# STM32WB55CGU6.net
KiCad netlist of a schematic drawn in Altium Designer
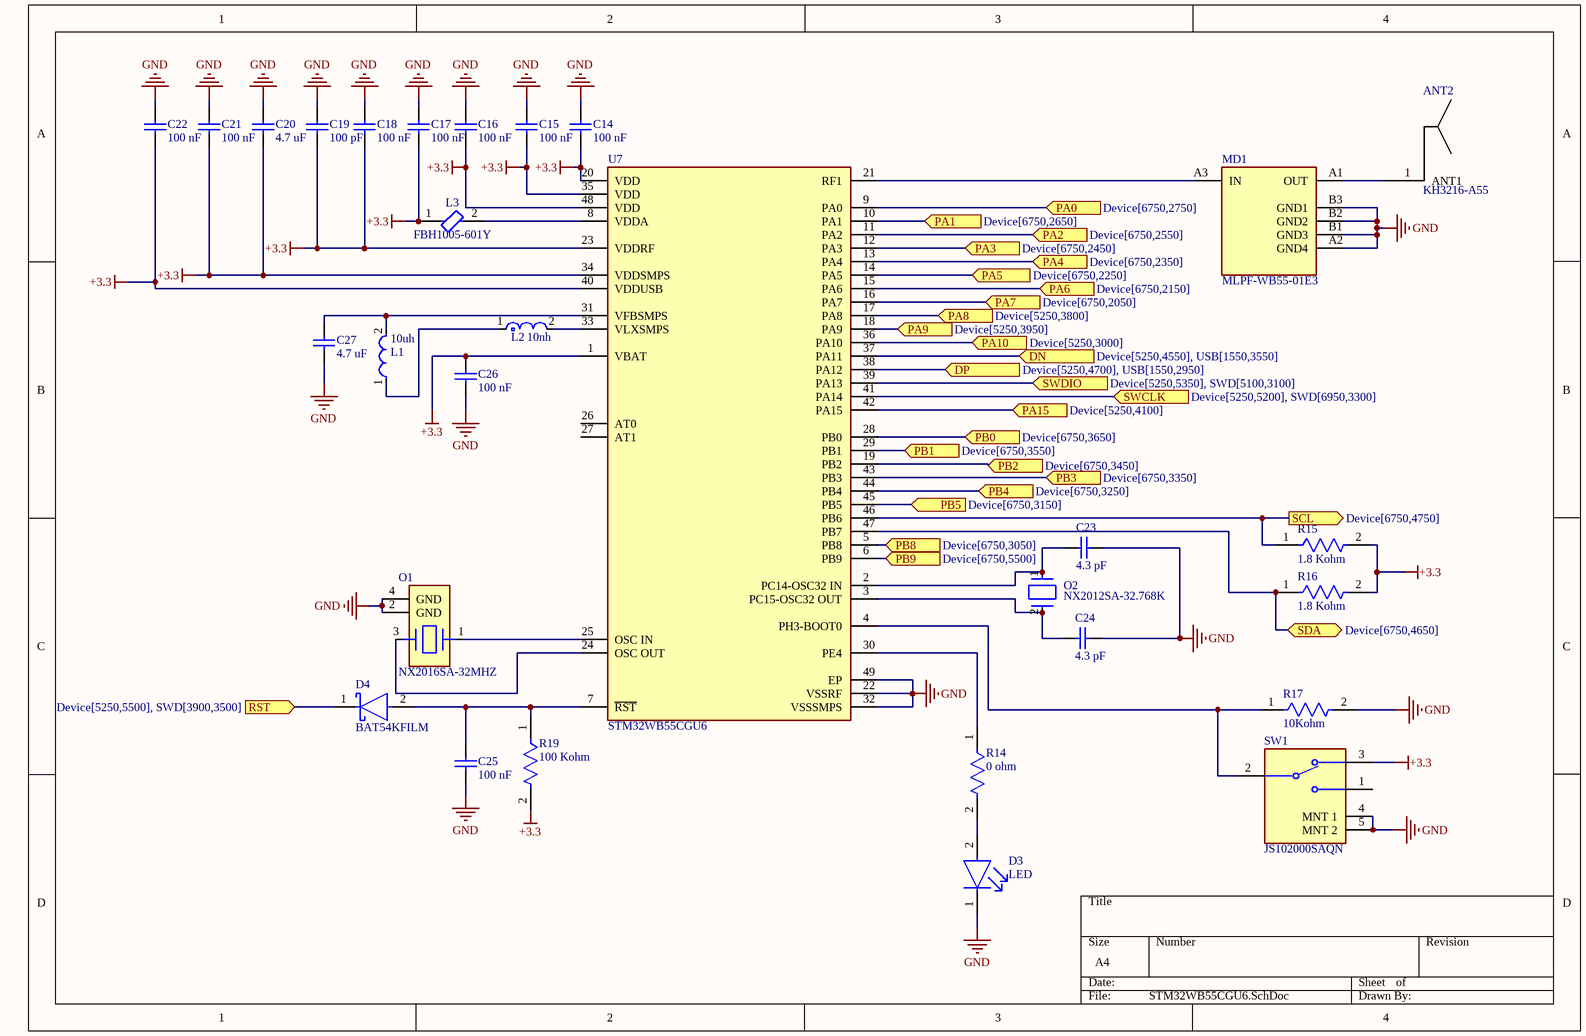
[diagram p0: STM32WB55CGU6.SchDoc]

(export (version "E")
  (design (tool "Eeschema 10.0.6"))
  (components
    (comp (ref "10uh")
      (value "L1")
      (footprint "FP-LQW15DN_00-MFG")
      (description "FIXED IND 10UH 120MA 5.405OHM")
      (libsource (lib "Altium Content Vault") (part "725321dda6339637d4d059423bc1c3c"))
    )
    (comp (ref "ANT2")
      (value "KH3216-A55")
      (footprint "KH3216-A55")
      (libsource (lib "Custom.") (part "KH3216-A55"))
    )
    (comp (ref "C14")
      (value "100 nF")
      (footprint "CAPC1005X55X25NL05T10")
      (fields (field (name "MANUFACTURER") "Murata") (field (name "PART NUMBER") "GRM155F50J684ZE01D"))
      (libsource (lib "Altium Content Vault") (part "CAP"))
    )
    (comp (ref "C15")
      (value "100 nF")
      (footprint "CAPC1005X55X25NL05T10")
      (fields (field (name "MANUFACTURER") "Murata") (field (name "PART NUMBER") "GRM155F50J684ZE01D"))
      (libsource (lib "Altium Content Vault") (part "CAP"))
    )
    (comp (ref "C16")
      (value "100 nF")
      (footprint "CAPC1005X55X25NL05T10")
      (fields (field (name "MANUFACTURER") "Murata") (field (name "PART NUMBER") "GRM155F50J684ZE01D"))
      (libsource (lib "Altium Content Vault") (part "CAP"))
    )
    (comp (ref "C17")
      (value "100 nF")
      (footprint "CAPC1005X55X25NL05T10")
      (fields (field (name "MANUFACTURER") "Murata") (field (name "PART NUMBER") "GRM155F50J684ZE01D"))
      (libsource (lib "Altium Content Vault") (part "CAP"))
    )
    (comp (ref "C18")
      (value "100 nF")
      (footprint "CAPC1005X55X25NL05T10")
      (fields (field (name "MANUFACTURER") "Murata") (field (name "PART NUMBER") "GRM155F50J684ZE01D"))
      (libsource (lib "Altium Content Vault") (part "CAP"))
    )
    (comp (ref "C19")
      (value "100 pF")
      (footprint "CAPC1005X55X25NL05T10")
      (fields (field (name "MANUFACTURER") "Murata") (field (name "PART NUMBER") "GRM155F50J684ZE01D"))
      (libsource (lib "Altium Content Vault") (part "CAP"))
    )
    (comp (ref "C20")
      (value "4.7 uF")
      (footprint "CAPC1005X55X25NL05T10")
      (fields (field (name "MANUFACTURER") "Murata") (field (name "PART NUMBER") "GRM155F50J684ZE01D"))
      (libsource (lib "Altium Content Vault") (part "CAP"))
    )
    (comp (ref "C21")
      (value "100 nF")
      (footprint "CAPC1005X55X25NL05T10")
      (fields (field (name "MANUFACTURER") "Murata") (field (name "PART NUMBER") "GRM155F50J684ZE01D"))
      (libsource (lib "Altium Content Vault") (part "CAP"))
    )
    (comp (ref "C22")
      (value "100 nF")
      (footprint "CAPC1005X55X25NL05T10")
      (fields (field (name "MANUFACTURER") "Murata") (field (name "PART NUMBER") "GRM155F50J684ZE01D"))
      (libsource (lib "Altium Content Vault") (part "CAP"))
    )
    (comp (ref "C23")
      (value "4.3 pF")
      (footprint "CAPC1005X55X25NL05T10")
      (fields (field (name "MANUFACTURER") "Murata") (field (name "PART NUMBER") "GRM155F50J684ZE01D"))
      (libsource (lib "Altium Content Vault") (part "CAP"))
    )
    (comp (ref "C24")
      (value "4.3 pF")
      (footprint "CAPC1005X55X25NL05T10")
      (fields (field (name "MANUFACTURER") "Murata") (field (name "PART NUMBER") "GRM155F50J684ZE01D"))
      (libsource (lib "Altium Content Vault") (part "CAP"))
    )
    (comp (ref "C25")
      (value "100 nF")
      (footprint "CAPC1005X55X25NL05T10")
      (fields (field (name "MANUFACTURER") "Murata") (field (name "PART NUMBER") "GRM155F50J684ZE01D"))
      (libsource (lib "Altium Content Vault") (part "CAP"))
    )
    (comp (ref "C26")
      (value "100 nF")
      (footprint "CAPC1005X55X25NL05T10")
      (fields (field (name "MANUFACTURER") "Murata") (field (name "PART NUMBER") "GRM155F50J684ZE01D"))
      (libsource (lib "Altium Content Vault") (part "CAP"))
    )
    (comp (ref "C27")
      (value "4.7 uF")
      (footprint "CAPC1005X55X25NL05T10")
      (fields (field (name "MANUFACTURER") "Murata") (field (name "PART NUMBER") "GRM155F50J684ZE01D"))
      (libsource (lib "Altium Content Vault") (part "CAP"))
    )
    (comp (ref "D3")
      (value "LED")
      (footprint "FP-SML-P11MTT86-MFG")
      (description "LED YELLOW/GREEN CLEAR 1006 SMD")
      (libsource (lib "Altium Content Vault") (part "8706943c75ba83719d021d2fdc84c58"))
    )
    (comp (ref "D4")
      (value "BAT54KFILM")
      (footprint "FP-SOD-523-MFG")
      (description "DIODE SCHOTTKY 40V 300MA SOD523")
      (fields
        (field (name "OCTOPART") "https://octopart.com/bat54kfilm-stmicroelectronics-39618022")
        (field (name "MANUFACTURER") "STMicroelectronics")
      )
      (libsource (lib "Altium Content Vault") (part "1d6ec82d83fb6aee721767c19dac4b9"))
    )
    (comp (ref "L2")
      (value "10nh")
      (footprint "FP-LQG15WH_02-MFG")
      (description "Multilayer type Inductor for Automotive 10nH ±5% 0.19Ω 500mA 0402")
      (fields (field (name "TOLERANCE") "5%"))
      (libsource (lib "Altium Content Vault") (part "4cc4b267dca4c8e51f7102f422741d8"))
    )
    (comp (ref "L3")
      (value "FBH1005-601Y")
      (footprint "FP-BLM15-0_05-MFG")
      (description "Chip Ferrite Bead, 0402, 600Ω @ 100MHz, 0.52Ω, 25%, 300mA")
      (fields (field (name "TOLERANCE") "25%"))
      (libsource (lib "Altium Content Vault") (part "5f30dd21d616792df468990f7003faa"))
    )
    (comp (ref "MD1")
      (value "MLPF-WB55-01E3")
      (footprint "FP-MLPF-WB55-01E3-MFG")
      (description "RF FILTER LOW PASS 2.45GHZ 6SMD")
      (libsource (lib "Altium Content Vault") (part "51e28da9fe7b2e4e5e03ac85244eada"))
    )
    (comp (ref "O1")
      (value "NX2016SA-32MHZ")
      (footprint "FP-NX2016SA-MFG")
      (description "CRYSTAL 32.0000MHZ 8PF SMD")
      (libsource (lib "Altium Content Vault") (part "0d11ad3ca7be055efd3b4f344707230"))
    )
    (comp (ref "O2")
      (value "NX2012SA-32.768K")
      (footprint "FP-NX2012SA-MFG")
      (description "CRYSTAL 32.7680KHZ 12.5PF SMD")
      (libsource (lib "Altium Content Vault") (part "c23a69dc6c9e2f18f2079038eb95dd1"))
    )
    (comp (ref "R14")
      (value "0 ohm")
      (footprint "FP-RC1005-IPC_C")
      (description "Res Thick Film 0402 1.87kΩ 1% 0.063W ±100ppm/°C Molded SMD T/R")
      (fields (field (name "TOLERANCE") "1%"))
      (libsource (lib "Altium Content Vault") (part "1029c3af85768c4190bb7ad29bc67b5"))
    )
    (comp (ref "R15")
      (value "1.8 Kohm")
      (footprint "FP-RC1005-IPC_C")
      (description "Res Thick Film 0402 1.87kΩ 1% 0.063W ±100ppm/°C Molded SMD T/R")
      (fields (field (name "TOLERANCE") "1%"))
      (libsource (lib "Altium Content Vault") (part "1029c3af85768c4190bb7ad29bc67b5"))
    )
    (comp (ref "R16")
      (value "1.8 Kohm")
      (footprint "FP-RC1005-IPC_C")
      (description "Res Thick Film 0402 1.87kΩ 1% 0.063W ±100ppm/°C Molded SMD T/R")
      (fields (field (name "TOLERANCE") "1%"))
      (libsource (lib "Altium Content Vault") (part "1029c3af85768c4190bb7ad29bc67b5"))
    )
    (comp (ref "R17")
      (value "10Kohm")
      (footprint "FP-RC1005-IPC_C")
      (description "Res Thick Film 0402 1.87kΩ 1% 0.063W ±100ppm/°C Molded SMD T/R")
      (fields (field (name "TOLERANCE") "1%"))
      (libsource (lib "Altium Content Vault") (part "1029c3af85768c4190bb7ad29bc67b5"))
    )
    (comp (ref "R19")
      (value "100 Kohm")
      (footprint "FP-RC1005-IPC_C")
      (description "Res Thick Film 0402 1.87kΩ 1% 0.063W ±100ppm/°C Molded SMD T/R")
      (fields (field (name "TOLERANCE") "1%"))
      (libsource (lib "Altium Content Vault") (part "1029c3af85768c4190bb7ad29bc67b5"))
    )
    (comp (ref "SW1")
      (value "JS102000SAQN")
      (footprint "FP-JS102000SAQN-MFG")
      (description "SWITCH SLIDE SPDT 1MA 5V")
      (libsource (lib "Altium Content Vault") (part "6887e5fe807d9c5c2853bed39bc55bf"))
    )
    (comp (ref "U7")
      (value "STM32WB55CGU6")
      (footprint "FP-STM32WB55CGU6-MFG")
      (description "ULTRA-LOW-POWER DUAL CORE ARM CO")
      (fields
        (field (name "OCTOPART") "https://octopart.com/stm32wb55cgu6-stmicroelectronics-98750847")
        (field (name "MANUFACTURER") "STMicroelectronics")
      )
      (libsource (lib "Altium Content Vault") (part "9d9ca7f3567da95c474f3f549f05e68"))
    )
  )
  (nets
    (net (code "1") (name "+3.3") (class "Default")
      (node (ref "C14") (pin "1") (pinfunction "1_1") (pintype "passive"))
      (node (ref "C15") (pin "2") (pinfunction "2_2") (pintype "passive"))
      (node (ref "C16") (pin "1") (pinfunction "1_1") (pintype "passive"))
      (node (ref "C17") (pin "2") (pinfunction "2_2") (pintype "passive"))
      (node (ref "C18") (pin "1") (pinfunction "1_1") (pintype "passive"))
      (node (ref "C19") (pin "2") (pinfunction "2_2") (pintype "passive"))
      (node (ref "C20") (pin "2") (pinfunction "2_2") (pintype "passive"))
      (node (ref "C21") (pin "1") (pinfunction "1_1") (pintype "passive"))
      (node (ref "C22") (pin "2") (pinfunction "2_2") (pintype "passive"))
      (node (ref "C26") (pin "2") (pinfunction "2_2") (pintype "passive"))
      (node (ref "L3") (pin "1") (pinfunction "1_1") (pintype "passive"))
      (node (ref "R15") (pin "2") (pinfunction "2_2") (pintype "passive"))
      (node (ref "R16") (pin "2") (pinfunction "2_2") (pintype "passive"))
      (node (ref "R19") (pin "2") (pinfunction "2_2") (pintype "passive"))
      (node (ref "SW1") (pin "3") (pinfunction "3_3") (pintype "passive"))
      (node (ref "U7") (pin "1") (pinfunction "VBAT_1") (pintype "passive"))
      (node (ref "U7") (pin "20") (pinfunction "VDD_20") (pintype "passive"))
      (node (ref "U7") (pin "23") (pinfunction "VDDRF_23") (pintype "passive"))
      (node (ref "U7") (pin "34") (pinfunction "VDDSMPS_34") (pintype "passive"))
      (node (ref "U7") (pin "35") (pinfunction "VDD_35") (pintype "passive"))
      (node (ref "U7") (pin "40") (pinfunction "VDDUSB_40") (pintype "passive"))
      (node (ref "U7") (pin "48") (pinfunction "VDD_48") (pintype "passive"))
    )
    (net (code "2") (name "/DN") (class "Default")
      (node (ref "U7") (pin "37") (pinfunction "PA11_37") (pintype "passive"))
    )
    (net (code "3") (name "/DP") (class "Default")
      (node (ref "U7") (pin "38") (pinfunction "PA12_38") (pintype "passive"))
    )
    (net (code "4") (name "/PA0") (class "Default")
      (node (ref "U7") (pin "9") (pinfunction "PA0_9") (pintype "passive"))
    )
    (net (code "5") (name "/PA1") (class "Default")
      (node (ref "U7") (pin "10") (pinfunction "PA1_10") (pintype "passive"))
    )
    (net (code "6") (name "/PA2") (class "Default")
      (node (ref "U7") (pin "11") (pinfunction "PA2_11") (pintype "passive"))
    )
    (net (code "7") (name "/PA3") (class "Default")
      (node (ref "U7") (pin "12") (pinfunction "PA3_12") (pintype "passive"))
    )
    (net (code "8") (name "/PA4") (class "Default")
      (node (ref "U7") (pin "13") (pinfunction "PA4_13") (pintype "passive"))
    )
    (net (code "9") (name "/PA5") (class "Default")
      (node (ref "U7") (pin "14") (pinfunction "PA5_14") (pintype "passive"))
    )
    (net (code "10") (name "/PA6") (class "Default")
      (node (ref "U7") (pin "15") (pinfunction "PA6_15") (pintype "passive"))
    )
    (net (code "11") (name "/PA7") (class "Default")
      (node (ref "U7") (pin "16") (pinfunction "PA7_16") (pintype "passive"))
    )
    (net (code "12") (name "/PA8") (class "Default")
      (node (ref "U7") (pin "17") (pinfunction "PA8_17") (pintype "passive"))
    )
    (net (code "13") (name "/PA9") (class "Default")
      (node (ref "U7") (pin "18") (pinfunction "PA9_18") (pintype "passive"))
    )
    (net (code "14") (name "/PA10") (class "Default")
      (node (ref "U7") (pin "36") (pinfunction "PA10_36") (pintype "passive"))
    )
    (net (code "15") (name "/PA15") (class "Default")
      (node (ref "U7") (pin "42") (pinfunction "PA15_42") (pintype "passive"))
    )
    (net (code "16") (name "/PB0") (class "Default")
      (node (ref "U7") (pin "28") (pinfunction "PB0_28") (pintype "passive"))
    )
    (net (code "17") (name "/PB1") (class "Default")
      (node (ref "U7") (pin "29") (pinfunction "PB1_29") (pintype "passive"))
    )
    (net (code "18") (name "/PB2") (class "Default")
      (node (ref "U7") (pin "19") (pinfunction "PB2_19") (pintype "passive"))
    )
    (net (code "19") (name "/PB3") (class "Default")
      (node (ref "U7") (pin "43") (pinfunction "PB3_43") (pintype "passive"))
    )
    (net (code "20") (name "/PB4") (class "Default")
      (node (ref "U7") (pin "44") (pinfunction "PB4_44") (pintype "passive"))
    )
    (net (code "21") (name "/PB5") (class "Default")
      (node (ref "U7") (pin "45") (pinfunction "PB5_45") (pintype "passive"))
    )
    (net (code "22") (name "/PB8") (class "Default")
      (node (ref "U7") (pin "5") (pinfunction "PB8_5") (pintype "passive"))
    )
    (net (code "23") (name "/PB9") (class "Default")
      (node (ref "U7") (pin "6") (pinfunction "PB9_6") (pintype "passive"))
    )
    (net (code "24") (name "/RST") (class "Default")
      (node (ref "D4") (pin "1") (pinfunction "C_1") (pintype "passive"))
    )
    (net (code "25") (name "/SCL") (class "Default")
      (node (ref "R15") (pin "1") (pinfunction "1_1") (pintype "passive"))
      (node (ref "U7") (pin "46") (pinfunction "PB6_46") (pintype "passive"))
    )
    (net (code "26") (name "/SDA") (class "Default")
      (node (ref "R16") (pin "1") (pinfunction "1_1") (pintype "passive"))
      (node (ref "U7") (pin "47") (pinfunction "PB7_47") (pintype "passive"))
    )
    (net (code "27") (name "/SWCLK") (class "Default")
      (node (ref "U7") (pin "41") (pinfunction "PA14_41") (pintype "passive"))
    )
    (net (code "28") (name "/SWDIO") (class "Default")
      (node (ref "U7") (pin "39") (pinfunction "PA13_39") (pintype "passive"))
    )
    (net (code "29") (name "GND") (class "Default")
      (node (ref "C14") (pin "2") (pinfunction "2_2") (pintype "passive"))
      (node (ref "C15") (pin "1") (pinfunction "1_1") (pintype "passive"))
      (node (ref "C16") (pin "2") (pinfunction "2_2") (pintype "passive"))
      (node (ref "C17") (pin "1") (pinfunction "1_1") (pintype "passive"))
      (node (ref "C18") (pin "2") (pinfunction "2_2") (pintype "passive"))
      (node (ref "C19") (pin "1") (pinfunction "1_1") (pintype "passive"))
      (node (ref "C20") (pin "1") (pinfunction "1_1") (pintype "passive"))
      (node (ref "C21") (pin "2") (pinfunction "2_2") (pintype "passive"))
      (node (ref "C22") (pin "1") (pinfunction "1_1") (pintype "passive"))
      (node (ref "C23") (pin "2") (pinfunction "2_2") (pintype "passive"))
      (node (ref "C24") (pin "1") (pinfunction "1_1") (pintype "passive"))
      (node (ref "C25") (pin "1") (pinfunction "1_1") (pintype "passive"))
      (node (ref "C26") (pin "1") (pinfunction "1_1") (pintype "passive"))
      (node (ref "C27") (pin "2") (pinfunction "2_2") (pintype "passive"))
      (node (ref "D3") (pin "1") (pinfunction "C_1") (pintype "passive"))
      (node (ref "MD1") (pin "A2") (pinfunction "GND4_A2") (pintype "power_in"))
      (node (ref "MD1") (pin "B1") (pinfunction "GND3_B1") (pintype "power_in"))
      (node (ref "MD1") (pin "B2") (pinfunction "GND2_B2") (pintype "power_in"))
      (node (ref "MD1") (pin "B3") (pinfunction "GND1_B3") (pintype "power_in"))
      (node (ref "O1") (pin "2") (pinfunction "GND_2") (pintype "power_in"))
      (node (ref "O1") (pin "4") (pinfunction "GND_4") (pintype "power_in"))
      (node (ref "R17") (pin "2") (pinfunction "2_2") (pintype "passive"))
      (node (ref "SW1") (pin "4") (pinfunction "MNT_1_4") (pintype "passive"))
      (node (ref "SW1") (pin "5") (pinfunction "MNT_2_5") (pintype "passive"))
      (node (ref "U7") (pin "22") (pinfunction "VSSRF_22") (pintype "passive"))
      (node (ref "U7") (pin "32") (pinfunction "VSSSMPS_32") (pintype "passive"))
      (node (ref "U7") (pin "49") (pinfunction "EP_49") (pintype "power_in"))
    )
    (net (code "30") (name "Net-(10uh-Pad1)") (class "Default")
      (node (ref "10uh") (pin "1") (pinfunction "1_1") (pintype "passive"))
      (node (ref "L2") (pin "1") (pinfunction "1_1") (pintype "passive"))
    )
    (net (code "31") (name "Net-(ANT2-ANT1)") (class "Default")
      (node (ref "ANT2") (pin "1") (pinfunction "ANT1_1") (pintype "passive"))
      (node (ref "MD1") (pin "A1") (pinfunction "OUT_A1") (pintype "passive"))
    )
    (net (code "32") (name "Net-(D3-A)") (class "Default")
      (node (ref "D3") (pin "2") (pinfunction "A_2") (pintype "passive"))
      (node (ref "R14") (pin "2") (pinfunction "2_2") (pintype "passive"))
    )
    (net (code "33") (name "Net-(D4-A)") (class "Default")
      (node (ref "C25") (pin "2") (pinfunction "2_2") (pintype "passive"))
      (node (ref "D4") (pin "2") (pinfunction "A_2") (pintype "passive"))
      (node (ref "R19") (pin "1") (pinfunction "1_1") (pintype "passive"))
      (node (ref "U7") (pin "7") (pinfunction "~{RST}_7") (pintype "passive"))
    )
    (net (code "34") (name "Net-(MD1-IN)") (class "Default")
      (node (ref "MD1") (pin "A3") (pinfunction "IN_A3") (pintype "power_in"))
      (node (ref "U7") (pin "21") (pinfunction "RF1_21") (pintype "passive"))
    )
    (net (code "35") (name "Net-(SW1-C)") (class "Default")
      (node (ref "R17") (pin "1") (pinfunction "1_1") (pintype "passive"))
      (node (ref "SW1") (pin "2") (pinfunction "C_2") (pintype "passive"))
      (node (ref "U7") (pin "4") (pinfunction "PH3-BOOT0_4") (pintype "passive"))
    )
    (net (code "36") (name "Net-(U7-OSC_IN)") (class "Default")
      (node (ref "O1") (pin "1") (pinfunction "1_1") (pintype "passive"))
      (node (ref "U7") (pin "25") (pinfunction "OSC_IN_25") (pintype "passive"))
    )
    (net (code "37") (name "Net-(U7-OSC_OUT)") (class "Default")
      (node (ref "O1") (pin "3") (pinfunction "3_3") (pintype "passive"))
      (node (ref "U7") (pin "24") (pinfunction "OSC_OUT_24") (pintype "passive"))
    )
    (net (code "38") (name "Net-(U7-PC14-OSC32_IN)") (class "Default")
      (node (ref "C23") (pin "1") (pinfunction "1_1") (pintype "passive"))
      (node (ref "O2") (pin "1") (pinfunction "1_1") (pintype "passive"))
      (node (ref "U7") (pin "2") (pinfunction "PC14-OSC32_IN_2") (pintype "passive"))
    )
    (net (code "39") (name "Net-(U7-PC15-OSC32_OUT)") (class "Default")
      (node (ref "C24") (pin "2") (pinfunction "2_2") (pintype "passive"))
      (node (ref "O2") (pin "2") (pinfunction "2_2") (pintype "passive"))
      (node (ref "U7") (pin "3") (pinfunction "PC15-OSC32_OUT_3") (pintype "passive"))
    )
    (net (code "40") (name "Net-(U7-PE4)") (class "Default")
      (node (ref "R14") (pin "1") (pinfunction "1_1") (pintype "passive"))
      (node (ref "U7") (pin "30") (pinfunction "PE4_30") (pintype "passive"))
    )
    (net (code "41") (name "Net-(U7-VDDA)") (class "Default")
      (node (ref "L3") (pin "2") (pinfunction "2_2") (pintype "passive"))
      (node (ref "U7") (pin "8") (pinfunction "VDDA_8") (pintype "passive"))
    )
    (net (code "42") (name "Net-(U7-VFBSMPS)") (class "Default")
      (node (ref "10uh") (pin "2") (pinfunction "2_2") (pintype "passive"))
      (node (ref "C27") (pin "1") (pinfunction "1_1") (pintype "passive"))
      (node (ref "U7") (pin "31") (pinfunction "VFBSMPS_31") (pintype "passive"))
    )
    (net (code "43") (name "Net-(U7-VLXSMPS)") (class "Default")
      (node (ref "L2") (pin "2") (pinfunction "2_2") (pintype "passive"))
      (node (ref "U7") (pin "33") (pinfunction "VLXSMPS_33") (pintype "passive"))
    )
    (net (code "44") (name "unconnected-(SW1-Pad1)") (class "Default")
      (node (ref "SW1") (pin "1") (pinfunction "1_1") (pintype "passive"))
    )
    (net (code "45") (name "unconnected-(U7-AT0-Pad26)") (class "Default")
      (node (ref "U7") (pin "26") (pinfunction "AT0_26") (pintype "passive"))
    )
    (net (code "46") (name "unconnected-(U7-AT1-Pad27)") (class "Default")
      (node (ref "U7") (pin "27") (pinfunction "AT1_27") (pintype "passive"))
    )
  )
)
